# main.net
KiCad netlist of a schematic drawn in Altium Designer
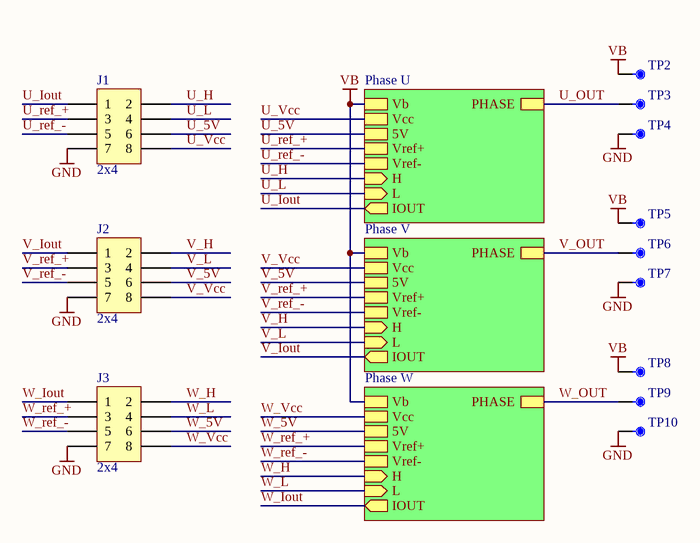
[diagram p0: main.SchDoc]

(export (version "E")
  (design (tool "Eeschema 10.0.6"))
  (components
    (comp (ref "J1")
      (value "2x4")
      (footprint "HDR-SMD_8P-P2.54-V-M-R2-C4-LS8.0")
      (description "2x4 2.54mm PH-00668")
      (libsource (lib "Schlib1") (part "Header 8"))
    )
    (comp (ref "J2")
      (value "2x4")
      (footprint "HDR-SMD_8P-P2.54-V-M-R2-C4-LS8.0")
      (description "2x4 2.54mm PH-00668")
      (libsource (lib "Schlib1") (part "Header 8"))
    )
    (comp (ref "J3")
      (value "2x4")
      (footprint "HDR-SMD_8P-P2.54-V-M-R2-C4-LS8.0")
      (description "2x4 2.54mm PH-00668")
      (libsource (lib "Schlib1") (part "Header 8"))
    )
    (comp (ref "TP2")
      (value "~")
      (footprint "TP2030_SMD")
      (libsource (lib "Miscellaneous Devices") (part "TP_Dup1"))
    )
    (comp (ref "TP3")
      (value "~")
      (footprint "TP2030_SMD")
      (libsource (lib "Miscellaneous Devices") (part "TP_Dup1"))
    )
    (comp (ref "TP4")
      (value "~")
      (footprint "TP2030_SMD")
      (libsource (lib "Miscellaneous Devices") (part "TP_Dup1"))
    )
    (comp (ref "TP5")
      (value "~")
      (footprint "TP2030_SMD")
      (libsource (lib "Miscellaneous Devices") (part "TP_Dup1"))
    )
    (comp (ref "TP6")
      (value "~")
      (footprint "TP2030_SMD")
      (libsource (lib "Miscellaneous Devices") (part "TP_Dup1"))
    )
    (comp (ref "TP7")
      (value "~")
      (footprint "TP2030_SMD")
      (libsource (lib "Miscellaneous Devices") (part "TP_Dup1"))
    )
    (comp (ref "TP8")
      (value "~")
      (footprint "TP2030_SMD")
      (libsource (lib "Miscellaneous Devices") (part "TP_Dup1"))
    )
    (comp (ref "TP9")
      (value "~")
      (footprint "TP2030_SMD")
      (libsource (lib "Miscellaneous Devices") (part "TP_Dup1"))
    )
    (comp (ref "TP10")
      (value "~")
      (footprint "TP2030_SMD")
      (libsource (lib "Miscellaneous Devices") (part "TP_Dup1"))
    )
  )
  (nets
    (net (code "1") (name "/U_5V") (class "Default")
      (node (ref "J1") (pin "6") (pinfunction "6_6") (pintype "passive"))
    )
    (net (code "2") (name "/U_H") (class "Default")
      (node (ref "J1") (pin "2") (pinfunction "2_2") (pintype "passive"))
    )
    (net (code "3") (name "/U_Iout") (class "Default")
      (node (ref "J1") (pin "1") (pinfunction "1_1") (pintype "passive"))
    )
    (net (code "4") (name "/U_L") (class "Default")
      (node (ref "J1") (pin "4") (pinfunction "4_4") (pintype "passive"))
    )
    (net (code "5") (name "/U_OUT") (class "Default")
      (node (ref "TP3") (pin "1") (pinfunction "1_1") (pintype "passive"))
    )
    (net (code "6") (name "/U_Vcc") (class "Default")
      (node (ref "J1") (pin "8") (pinfunction "8_8") (pintype "passive"))
    )
    (net (code "7") (name "/U_ref_+") (class "Default")
      (node (ref "J1") (pin "3") (pinfunction "3_3") (pintype "passive"))
    )
    (net (code "8") (name "/U_ref_-") (class "Default")
      (node (ref "J1") (pin "5") (pinfunction "5_5") (pintype "passive"))
    )
    (net (code "9") (name "/V_5V") (class "Default")
      (node (ref "J2") (pin "6") (pinfunction "6_6") (pintype "passive"))
    )
    (net (code "10") (name "/V_H") (class "Default")
      (node (ref "J2") (pin "2") (pinfunction "2_2") (pintype "passive"))
    )
    (net (code "11") (name "/V_Iout") (class "Default")
      (node (ref "J2") (pin "1") (pinfunction "1_1") (pintype "passive"))
    )
    (net (code "12") (name "/V_L") (class "Default")
      (node (ref "J2") (pin "4") (pinfunction "4_4") (pintype "passive"))
    )
    (net (code "13") (name "/V_OUT") (class "Default")
      (node (ref "TP6") (pin "1") (pinfunction "1_1") (pintype "passive"))
    )
    (net (code "14") (name "/V_Vcc") (class "Default")
      (node (ref "J2") (pin "8") (pinfunction "8_8") (pintype "passive"))
    )
    (net (code "15") (name "/V_ref_+") (class "Default")
      (node (ref "J2") (pin "3") (pinfunction "3_3") (pintype "passive"))
    )
    (net (code "16") (name "/V_ref_-") (class "Default")
      (node (ref "J2") (pin "5") (pinfunction "5_5") (pintype "passive"))
    )
    (net (code "17") (name "/W_5V") (class "Default")
      (node (ref "J3") (pin "6") (pinfunction "6_6") (pintype "passive"))
    )
    (net (code "18") (name "/W_H") (class "Default")
      (node (ref "J3") (pin "2") (pinfunction "2_2") (pintype "passive"))
    )
    (net (code "19") (name "/W_Iout") (class "Default")
      (node (ref "J3") (pin "1") (pinfunction "1_1") (pintype "passive"))
    )
    (net (code "20") (name "/W_L") (class "Default")
      (node (ref "J3") (pin "4") (pinfunction "4_4") (pintype "passive"))
    )
    (net (code "21") (name "/W_OUT") (class "Default")
      (node (ref "TP9") (pin "1") (pinfunction "1_1") (pintype "passive"))
    )
    (net (code "22") (name "/W_Vcc") (class "Default")
      (node (ref "J3") (pin "8") (pinfunction "8_8") (pintype "passive"))
    )
    (net (code "23") (name "/W_ref_+") (class "Default")
      (node (ref "J3") (pin "3") (pinfunction "3_3") (pintype "passive"))
    )
    (net (code "24") (name "/W_ref_-") (class "Default")
      (node (ref "J3") (pin "5") (pinfunction "5_5") (pintype "passive"))
    )
    (net (code "25") (name "GND") (class "Default")
      (node (ref "J1") (pin "7") (pinfunction "7_7") (pintype "passive"))
      (node (ref "J2") (pin "7") (pinfunction "7_7") (pintype "passive"))
      (node (ref "J3") (pin "7") (pinfunction "7_7") (pintype "passive"))
      (node (ref "TP10") (pin "1") (pinfunction "1_1") (pintype "passive"))
      (node (ref "TP4") (pin "1") (pinfunction "1_1") (pintype "passive"))
      (node (ref "TP7") (pin "1") (pinfunction "1_1") (pintype "passive"))
    )
    (net (code "26") (name "VB") (class "Default")
      (node (ref "TP2") (pin "1") (pinfunction "1_1") (pintype "passive"))
      (node (ref "TP5") (pin "1") (pinfunction "1_1") (pintype "passive"))
      (node (ref "TP8") (pin "1") (pinfunction "1_1") (pintype "passive"))
    )
  )
)
